# node-mcu-pack.net
KiCad netlist of a schematic drawn in EAGLE
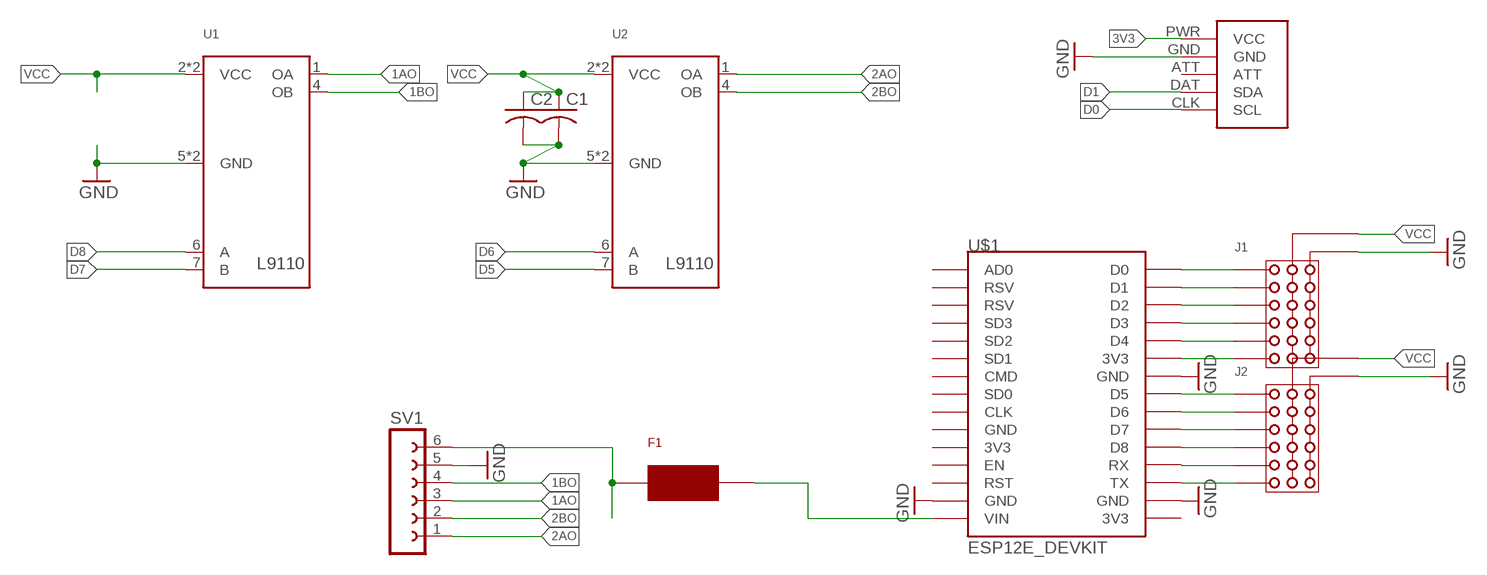
[diagram p0: schematic, sheet 1]

(export (version "E")
  (design (tool "Eeschema 10.0.6"))
  (components
    (comp (ref "C1")
      (value "C-USC0805")
      (footprint "eagle-import:C0805")
      (libsource (lib "eagle-import") (part "C-USC0805"))
    )
    (comp (ref "C2")
      (value "C-USC0805")
      (footprint "eagle-import:C0805")
      (libsource (lib "eagle-import") (part "C-USC0805"))
    )
    (comp (ref "F1")
      (value "0154")
      (footprint "eagle-import:0154")
      (libsource (lib "eagle-import") (part "0154"))
    )
    (comp (ref "J1")
      (value "IOBLOCK6")
      (footprint "eagle-import:IOBLOCK100MILX6")
      (libsource (lib "eagle-import") (part "IOBLOCK6"))
    )
    (comp (ref "J2")
      (value "IOBLOCK6")
      (footprint "eagle-import:IOBLOCK100MILX6")
      (libsource (lib "eagle-import") (part "IOBLOCK6"))
    )
    (comp (ref "SV1")
      (value "FE06-1")
      (footprint "eagle-import:FE06")
      (libsource (lib "eagle-import") (part "FE06-1"))
    )
    (comp (ref "U$1")
      (value "ESP12E_DEVKIT")
      (footprint "eagle-import:ESP12E_DEVKIT")
      (libsource (lib "eagle-import") (part "ESP12E_DEVKIT"))
    )
    (comp (ref "U$2")
      (value "WIICHUCKOUTIE")
      (footprint "eagle-import:CHUCK-OUTIE")
      (libsource (lib "eagle-import") (part "WIICHUCKOUTIE"))
    )
    (comp (ref "U1")
      (value "L9110SMT")
      (footprint "eagle-import:8S1")
      (libsource (lib "eagle-import") (part "L9110SMT"))
    )
    (comp (ref "U2")
      (value "L9110SMT")
      (footprint "eagle-import:8S1")
      (libsource (lib "eagle-import") (part "L9110SMT"))
    )
  )
  (nets
    (net (code "1") (name "1AO") (class "Default")
      (node (ref "SV1") (pin "3") (pinfunction "3_3") (pintype "passive"))
      (node (ref "U1") (pin "1") (pinfunction "OA_1") (pintype "bidirectional"))
    )
    (net (code "2") (name "1BO") (class "Default")
      (node (ref "SV1") (pin "4") (pinfunction "4_4") (pintype "passive"))
      (node (ref "U1") (pin "4") (pinfunction "OB_4") (pintype "bidirectional"))
    )
    (net (code "3") (name "2AO") (class "Default")
      (node (ref "SV1") (pin "1") (pinfunction "1_1") (pintype "passive"))
      (node (ref "U2") (pin "1") (pinfunction "OA_1") (pintype "bidirectional"))
    )
    (net (code "4") (name "2BO") (class "Default")
      (node (ref "SV1") (pin "2") (pinfunction "2_2") (pintype "passive"))
      (node (ref "U2") (pin "4") (pinfunction "OB_4") (pintype "bidirectional"))
    )
    (net (code "5") (name "3V3") (class "Default")
      (node (ref "J1") (pin "P$6") (pinfunction "P$6_P$6") (pintype "bidirectional"))
      (node (ref "U$1") (pin "3V3@1") (pinfunction "3V3_3V3@1") (pintype "bidirectional"))
      (node (ref "U$2") (pin "PWR") (pinfunction "VCC_PWR") (pintype "bidirectional"))
    )
    (net (code "6") (name "D0") (class "Default")
      (node (ref "J1") (pin "P$1") (pinfunction "P$1_P$1") (pintype "bidirectional"))
      (node (ref "U$1") (pin "D0") (pinfunction "D0_D0") (pintype "bidirectional"))
      (node (ref "U$2") (pin "CLK") (pinfunction "SCL_CLK") (pintype "bidirectional"))
    )
    (net (code "7") (name "D1") (class "Default")
      (node (ref "J1") (pin "P$2") (pinfunction "P$2_P$2") (pintype "bidirectional"))
      (node (ref "U$1") (pin "D1") (pinfunction "D1_D1") (pintype "bidirectional"))
      (node (ref "U$2") (pin "DAT") (pinfunction "SDA_DAT") (pintype "bidirectional"))
    )
    (net (code "8") (name "D5") (class "Default")
      (node (ref "J2") (pin "P$1") (pinfunction "P$1_P$1") (pintype "bidirectional"))
      (node (ref "U$1") (pin "D5") (pinfunction "D5_D5") (pintype "bidirectional"))
      (node (ref "U2") (pin "7") (pinfunction "B_7") (pintype "bidirectional"))
    )
    (net (code "9") (name "D6") (class "Default")
      (node (ref "J2") (pin "P$2") (pinfunction "P$2_P$2") (pintype "bidirectional"))
      (node (ref "U$1") (pin "D6") (pinfunction "D6_D6") (pintype "bidirectional"))
      (node (ref "U2") (pin "6") (pinfunction "A_6") (pintype "bidirectional"))
    )
    (net (code "10") (name "D7") (class "Default")
      (node (ref "J2") (pin "P$3") (pinfunction "P$3_P$3") (pintype "bidirectional"))
      (node (ref "U$1") (pin "D7") (pinfunction "D7_D7") (pintype "bidirectional"))
      (node (ref "U1") (pin "7") (pinfunction "B_7") (pintype "bidirectional"))
    )
    (net (code "11") (name "D8") (class "Default")
      (node (ref "J2") (pin "P$4") (pinfunction "P$4_P$4") (pintype "bidirectional"))
      (node (ref "U$1") (pin "D8") (pinfunction "D8_D8") (pintype "bidirectional"))
      (node (ref "U1") (pin "6") (pinfunction "A_6") (pintype "bidirectional"))
    )
    (net (code "12") (name "GND") (class "Default")
      (node (ref "C1") (pin "2") (pinfunction "2_2") (pintype "passive"))
      (node (ref "C2") (pin "2") (pinfunction "2_2") (pintype "passive"))
      (node (ref "J1") (pin "G1") (pinfunction "P$8_G1") (pintype "bidirectional"))
      (node (ref "J1") (pin "G2") (pinfunction "P$8_G2") (pintype "bidirectional"))
      (node (ref "J1") (pin "G3") (pinfunction "P$8_G3") (pintype "bidirectional"))
      (node (ref "J1") (pin "G4") (pinfunction "P$8_G4") (pintype "bidirectional"))
      (node (ref "J1") (pin "G5") (pinfunction "P$8_G5") (pintype "bidirectional"))
      (node (ref "J1") (pin "G6") (pinfunction "P$8_G6") (pintype "bidirectional"))
      (node (ref "J2") (pin "G1") (pinfunction "P$8_G1") (pintype "bidirectional"))
      (node (ref "J2") (pin "G2") (pinfunction "P$8_G2") (pintype "bidirectional"))
      (node (ref "J2") (pin "G3") (pinfunction "P$8_G3") (pintype "bidirectional"))
      (node (ref "J2") (pin "G4") (pinfunction "P$8_G4") (pintype "bidirectional"))
      (node (ref "J2") (pin "G5") (pinfunction "P$8_G5") (pintype "bidirectional"))
      (node (ref "J2") (pin "G6") (pinfunction "P$8_G6") (pintype "bidirectional"))
      (node (ref "SV1") (pin "5") (pinfunction "5_5") (pintype "passive"))
      (node (ref "U$1") (pin "GND@1") (pinfunction "GND_GND@1") (pintype "bidirectional"))
      (node (ref "U$1") (pin "GND@2") (pinfunction "GND_GND@2") (pintype "bidirectional"))
      (node (ref "U$1") (pin "GND@3") (pinfunction "GND_GND@3") (pintype "bidirectional"))
      (node (ref "U$2") (pin "GND") (pinfunction "GND_GND") (pintype "bidirectional"))
      (node (ref "U1") (pin "5") (pinfunction "GND_5") (pintype "bidirectional"))
      (node (ref "U1") (pin "8") (pinfunction "GND_8") (pintype "bidirectional"))
      (node (ref "U2") (pin "5") (pinfunction "GND_5") (pintype "bidirectional"))
      (node (ref "U2") (pin "8") (pinfunction "GND_8") (pintype "bidirectional"))
    )
    (net (code "13") (name "Net-(F1-P$1)") (class "Default")
      (node (ref "F1") (pin "1") (pinfunction "P$1_1") (pintype "bidirectional"))
      (node (ref "SV1") (pin "6") (pinfunction "6_6") (pintype "passive"))
    )
    (net (code "14") (name "Net-(J1-PadP$3)") (class "Default")
      (node (ref "J1") (pin "P$3") (pinfunction "P$3_P$3") (pintype "bidirectional"))
      (node (ref "U$1") (pin "D2") (pinfunction "D2_D2") (pintype "bidirectional"))
    )
    (net (code "15") (name "Net-(J1-PadP$4)") (class "Default")
      (node (ref "J1") (pin "P$4") (pinfunction "P$4_P$4") (pintype "bidirectional"))
      (node (ref "U$1") (pin "D3") (pinfunction "D3_D3") (pintype "bidirectional"))
    )
    (net (code "16") (name "Net-(J1-PadP$5)") (class "Default")
      (node (ref "J1") (pin "P$5") (pinfunction "P$5_P$5") (pintype "bidirectional"))
      (node (ref "U$1") (pin "D4") (pinfunction "D4_D4") (pintype "bidirectional"))
    )
    (net (code "17") (name "Net-(J2-PadP$5)") (class "Default")
      (node (ref "J2") (pin "P$5") (pinfunction "P$5_P$5") (pintype "bidirectional"))
      (node (ref "U$1") (pin "RX") (pinfunction "RX_RX") (pintype "bidirectional"))
    )
    (net (code "18") (name "Net-(J2-PadP$6)") (class "Default")
      (node (ref "J2") (pin "P$6") (pinfunction "P$6_P$6") (pintype "bidirectional"))
      (node (ref "U$1") (pin "TX") (pinfunction "TX_TX") (pintype "bidirectional"))
    )
    (net (code "19") (name "VCC") (class "Default")
      (node (ref "C1") (pin "1") (pinfunction "1_1") (pintype "passive"))
      (node (ref "C2") (pin "1") (pinfunction "1_1") (pintype "passive"))
      (node (ref "F1") (pin "2") (pinfunction "P$2_2") (pintype "bidirectional"))
      (node (ref "J1") (pin "P1") (pinfunction "P$7_P1") (pintype "bidirectional"))
      (node (ref "J1") (pin "P2") (pinfunction "P$7_P2") (pintype "bidirectional"))
      (node (ref "J1") (pin "P3") (pinfunction "P$7_P3") (pintype "bidirectional"))
      (node (ref "J1") (pin "P4") (pinfunction "P$7_P4") (pintype "bidirectional"))
      (node (ref "J1") (pin "P5") (pinfunction "P$7_P5") (pintype "bidirectional"))
      (node (ref "J1") (pin "P6") (pinfunction "P$7_P6") (pintype "bidirectional"))
      (node (ref "J2") (pin "P1") (pinfunction "P$7_P1") (pintype "bidirectional"))
      (node (ref "J2") (pin "P2") (pinfunction "P$7_P2") (pintype "bidirectional"))
      (node (ref "J2") (pin "P3") (pinfunction "P$7_P3") (pintype "bidirectional"))
      (node (ref "J2") (pin "P4") (pinfunction "P$7_P4") (pintype "bidirectional"))
      (node (ref "J2") (pin "P5") (pinfunction "P$7_P5") (pintype "bidirectional"))
      (node (ref "J2") (pin "P6") (pinfunction "P$7_P6") (pintype "bidirectional"))
      (node (ref "U$1") (pin "VIN") (pinfunction "VIN_VIN") (pintype "bidirectional"))
      (node (ref "U1") (pin "2") (pinfunction "VCC_2") (pintype "bidirectional"))
      (node (ref "U1") (pin "3") (pinfunction "VCC_3") (pintype "bidirectional"))
      (node (ref "U2") (pin "2") (pinfunction "VCC_2") (pintype "bidirectional"))
      (node (ref "U2") (pin "3") (pinfunction "VCC_3") (pintype "bidirectional"))
    )
    (net (code "20") (name "unconnected-(U$1-3V3-Pad3V3@0)") (class "Default")
      (node (ref "U$1") (pin "3V3@0") (pinfunction "3V3_3V3@0") (pintype "bidirectional"))
    )
    (net (code "21") (name "unconnected-(U$1-3V3-Pad3V3@2)") (class "Default")
      (node (ref "U$1") (pin "3V3@2") (pinfunction "3V3_3V3@2") (pintype "bidirectional"))
    )
    (net (code "22") (name "unconnected-(U$1-GND-PadGND@0)") (class "Default")
      (node (ref "U$1") (pin "GND@0") (pinfunction "GND_GND@0") (pintype "bidirectional"))
    )
    (net (code "23") (name "unconnected-(U$1-PadAD0)") (class "Default")
      (node (ref "U$1") (pin "AD0") (pinfunction "AD0_AD0") (pintype "bidirectional"))
    )
    (net (code "24") (name "unconnected-(U$1-PadCLK)") (class "Default")
      (node (ref "U$1") (pin "CLK") (pinfunction "CLK_CLK") (pintype "bidirectional"))
    )
    (net (code "25") (name "unconnected-(U$1-PadCMD)") (class "Default")
      (node (ref "U$1") (pin "CMD") (pinfunction "CMD_CMD") (pintype "bidirectional"))
    )
    (net (code "26") (name "unconnected-(U$1-PadEN)") (class "Default")
      (node (ref "U$1") (pin "EN") (pinfunction "EN_EN") (pintype "bidirectional"))
    )
    (net (code "27") (name "unconnected-(U$1-PadRST)") (class "Default")
      (node (ref "U$1") (pin "RST") (pinfunction "RST_RST") (pintype "bidirectional"))
    )
    (net (code "28") (name "unconnected-(U$1-PadSD0)") (class "Default")
      (node (ref "U$1") (pin "SD0") (pinfunction "SD0_SD0") (pintype "bidirectional"))
    )
    (net (code "29") (name "unconnected-(U$1-PadSD1)") (class "Default")
      (node (ref "U$1") (pin "SD1") (pinfunction "SD1_SD1") (pintype "bidirectional"))
    )
    (net (code "30") (name "unconnected-(U$1-PadSD2)") (class "Default")
      (node (ref "U$1") (pin "SD2") (pinfunction "SD2_SD2") (pintype "bidirectional"))
    )
    (net (code "31") (name "unconnected-(U$1-PadSD3)") (class "Default")
      (node (ref "U$1") (pin "SD3") (pinfunction "SD3_SD3") (pintype "bidirectional"))
    )
    (net (code "32") (name "unconnected-(U$1-RSV-PadRSV@0)") (class "Default")
      (node (ref "U$1") (pin "RSV@0") (pinfunction "RSV_RSV@0") (pintype "bidirectional"))
    )
    (net (code "33") (name "unconnected-(U$1-RSV-PadRSV@1)") (class "Default")
      (node (ref "U$1") (pin "RSV@1") (pinfunction "RSV_RSV@1") (pintype "bidirectional"))
    )
    (net (code "34") (name "unconnected-(U$2-PadATT)") (class "Default")
      (node (ref "U$2") (pin "ATT") (pinfunction "ATT_ATT") (pintype "bidirectional"))
    )
  )
)
